# PROC_partD__VSS.net
KiCad netlist of a schematic drawn in Altium Designer
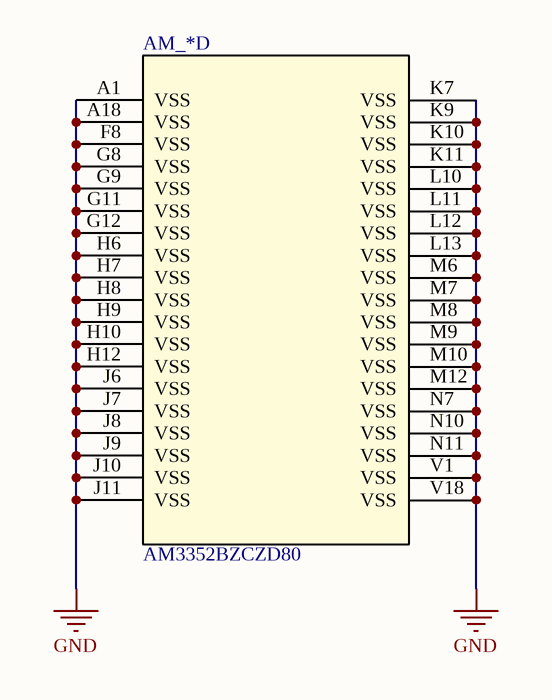
[diagram p0: PROC_partD_(VSS).SchDoc]

(export (version "E")
  (design (tool "Eeschema 10.0.6"))
  (components
    (comp (ref "AM_*")
      (value "AM3352BZCZD80")
      (footprint "BGA324C80P18X18_800X1508X1508")
      (description "Microprocesseur ARM")
      (libsource (lib "Michel") (part "AM3352BZCZD80"))
    )
  )
  (nets
    (net (code "1") (name "GND") (class "Default")
      (node (ref "AM_*") (pin "A1") (pinfunction "VSS_A1") (pintype "power_in"))
      (node (ref "AM_*") (pin "A18") (pinfunction "VSS_A18") (pintype "power_in"))
      (node (ref "AM_*") (pin "F8") (pinfunction "VSS_F8") (pintype "power_in"))
      (node (ref "AM_*") (pin "G11") (pinfunction "VSS_G11") (pintype "power_in"))
      (node (ref "AM_*") (pin "G12") (pinfunction "VSS_G12") (pintype "power_in"))
      (node (ref "AM_*") (pin "G8") (pinfunction "VSS_G8") (pintype "power_in"))
      (node (ref "AM_*") (pin "G9") (pinfunction "VSS_G9") (pintype "power_in"))
      (node (ref "AM_*") (pin "H10") (pinfunction "VSS_H10") (pintype "power_in"))
      (node (ref "AM_*") (pin "H12") (pinfunction "VSS_H12") (pintype "power_in"))
      (node (ref "AM_*") (pin "H6") (pinfunction "VSS_H6") (pintype "power_in"))
      (node (ref "AM_*") (pin "H7") (pinfunction "VSS_H7") (pintype "power_in"))
      (node (ref "AM_*") (pin "H8") (pinfunction "VSS_H8") (pintype "power_in"))
      (node (ref "AM_*") (pin "H9") (pinfunction "VSS_H9") (pintype "power_in"))
      (node (ref "AM_*") (pin "J10") (pinfunction "VSS_J10") (pintype "power_in"))
      (node (ref "AM_*") (pin "J11") (pinfunction "VSS_J11") (pintype "power_in"))
      (node (ref "AM_*") (pin "J6") (pinfunction "VSS_J6") (pintype "power_in"))
      (node (ref "AM_*") (pin "J7") (pinfunction "VSS_J7") (pintype "power_in"))
      (node (ref "AM_*") (pin "J8") (pinfunction "VSS_J8") (pintype "power_in"))
      (node (ref "AM_*") (pin "J9") (pinfunction "VSS_J9") (pintype "power_in"))
      (node (ref "AM_*") (pin "K10") (pinfunction "VSS_K10") (pintype "power_in"))
      (node (ref "AM_*") (pin "K11") (pinfunction "VSS_K11") (pintype "power_in"))
      (node (ref "AM_*") (pin "K7") (pinfunction "VSS_K7") (pintype "power_in"))
      (node (ref "AM_*") (pin "K9") (pinfunction "VSS_K9") (pintype "power_in"))
      (node (ref "AM_*") (pin "L10") (pinfunction "VSS_L10") (pintype "power_in"))
      (node (ref "AM_*") (pin "L11") (pinfunction "VSS_L11") (pintype "power_in"))
      (node (ref "AM_*") (pin "L12") (pinfunction "VSS_L12") (pintype "power_in"))
      (node (ref "AM_*") (pin "L13") (pinfunction "VSS_L13") (pintype "power_in"))
      (node (ref "AM_*") (pin "M10") (pinfunction "VSS_M10") (pintype "power_in"))
      (node (ref "AM_*") (pin "M12") (pinfunction "VSS_M12") (pintype "power_in"))
      (node (ref "AM_*") (pin "M6") (pinfunction "VSS_M6") (pintype "power_in"))
      (node (ref "AM_*") (pin "M7") (pinfunction "VSS_M7") (pintype "power_in"))
      (node (ref "AM_*") (pin "M8") (pinfunction "VSS_M8") (pintype "power_in"))
      (node (ref "AM_*") (pin "M9") (pinfunction "VSS_M9") (pintype "power_in"))
      (node (ref "AM_*") (pin "N10") (pinfunction "VSS_N10") (pintype "power_in"))
      (node (ref "AM_*") (pin "N11") (pinfunction "VSS_N11") (pintype "power_in"))
      (node (ref "AM_*") (pin "N7") (pinfunction "VSS_N7") (pintype "power_in"))
      (node (ref "AM_*") (pin "V1") (pinfunction "VSS_V1") (pintype "power_in"))
      (node (ref "AM_*") (pin "V18") (pinfunction "VSS_V18") (pintype "power_in"))
    )
  )
)
